# VerberBaby.net
KiCad netlist of a schematic drawn in EAGLE
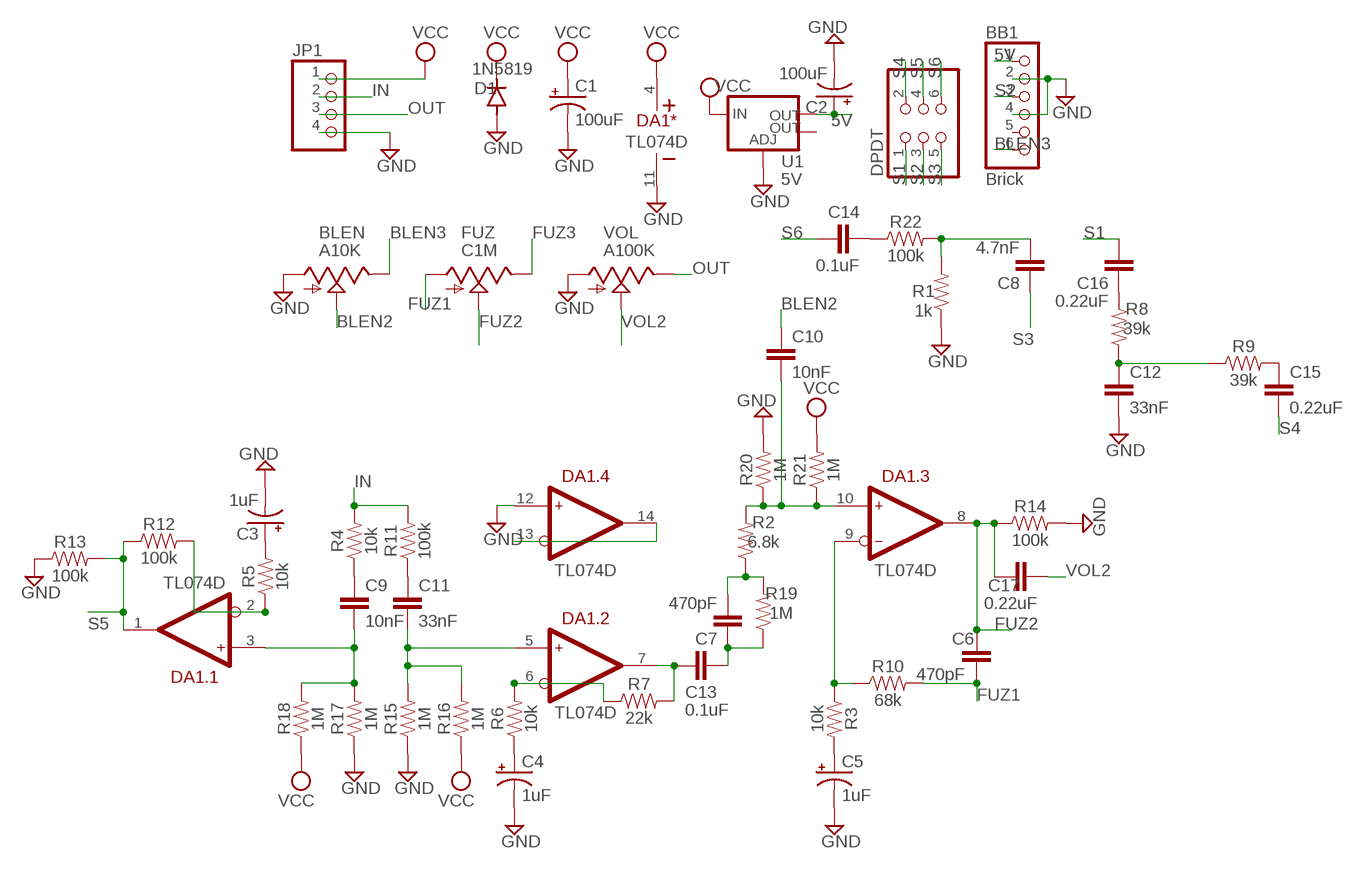
[diagram p0: schematic, sheet 1]

(export (version "E")
  (design (tool "Eeschema 10.0.6"))
  (components
    (comp (ref "BB1")
      (value "Brick")
      (footprint "eagle-import:1X06")
      (libsource (lib "eagle-import") (part "PINHD-1X6"))
    )
    (comp (ref "BLEN")
      (value "A10K")
      (footprint "eagle-import:9MM_SNAP-IN_POT")
      (libsource (lib "eagle-import") (part "9MM_SNAP-IN_POT_"))
    )
    (comp (ref "C1")
      (value "100uF")
      (footprint "eagle-import:PAN_B_SMD+THRU")
      (libsource (lib "eagle-import") (part "CAP_SMD+THRUPAN_B"))
    )
    (comp (ref "C2")
      (value "100uF")
      (footprint "eagle-import:PAN_B_SMD+THRU")
      (libsource (lib "eagle-import") (part "CAP_SMD+THRUPAN_B"))
    )
    (comp (ref "C3")
      (value "1uF")
      (footprint "eagle-import:PAN_B_SMD+THRU")
      (libsource (lib "eagle-import") (part "CAP_SMD+THRUPAN_B"))
    )
    (comp (ref "C4")
      (value "1uF")
      (footprint "eagle-import:PAN_B_SMD+THRU")
      (libsource (lib "eagle-import") (part "CAP_SMD+THRUPAN_B"))
    )
    (comp (ref "C5")
      (value "1uF")
      (footprint "eagle-import:PAN_B_SMD+THRU")
      (libsource (lib "eagle-import") (part "CAP_SMD+THRUPAN_B"))
    )
    (comp (ref "C6")
      (value "470pF")
      (footprint "eagle-import:0603")
      (libsource (lib "eagle-import") (part "470PF-0603-50V-5%"))
    )
    (comp (ref "C7")
      (value "470pF")
      (footprint "eagle-import:0603")
      (libsource (lib "eagle-import") (part "470PF-0603-50V-5%"))
    )
    (comp (ref "C8")
      (value "4.7nF")
      (footprint "eagle-import:0603")
      (libsource (lib "eagle-import") (part "4.7PF-0603-50V-5%"))
    )
    (comp (ref "C9")
      (value "10nF")
      (footprint "eagle-import:0603")
      (libsource (lib "eagle-import") (part "10NF-0603-50V-10%"))
    )
    (comp (ref "C10")
      (value "10nF")
      (footprint "eagle-import:0603")
      (libsource (lib "eagle-import") (part "10NF-0603-50V-10%"))
    )
    (comp (ref "C11")
      (value "33nF")
      (footprint "eagle-import:0603")
      (libsource (lib "eagle-import") (part "33NF-0603-50V-10%"))
    )
    (comp (ref "C12")
      (value "33nF")
      (footprint "eagle-import:0603")
      (libsource (lib "eagle-import") (part "33NF-0603-50V-10%"))
    )
    (comp (ref "C13")
      (value "0.1uF")
      (footprint "eagle-import:0603")
      (libsource (lib "eagle-import") (part "0.1UF-0603-25V-(+80/-20%)"))
    )
    (comp (ref "C14")
      (value "0.1uF")
      (footprint "eagle-import:0603")
      (libsource (lib "eagle-import") (part "0.1UF-0603-25V-(+80/-20%)"))
    )
    (comp (ref "C15")
      (value "0.22uF")
      (footprint "eagle-import:0603")
      (libsource (lib "eagle-import") (part "0.22UF-0603-25V-10%"))
    )
    (comp (ref "C16")
      (value "0.22uF")
      (footprint "eagle-import:0603")
      (libsource (lib "eagle-import") (part "0.22UF-0603-25V-10%"))
    )
    (comp (ref "C17")
      (value "0.22uF")
      (footprint "eagle-import:0603")
      (libsource (lib "eagle-import") (part "0.22UF-0603-25V-10%"))
    )
    (comp (ref "D1")
      (value "1N5819")
      (footprint "eagle-import:SOD123")
      (libsource (lib "eagle-import") (part "DIODE-SOD123"))
    )
    (comp (ref "DA1")
      (value "TL074D")
      (footprint "eagle-import:SO-14")
      (libsource (lib "eagle-import") (part "TL074D"))
    )
    (comp (ref "DPDT")
      (value "PINHD-2X3")
      (footprint "eagle-import:2X03")
      (libsource (lib "eagle-import") (part "PINHD-2X3"))
    )
    (comp (ref "FUZ")
      (value "C1M")
      (footprint "eagle-import:9MM_SNAP-IN_POT")
      (libsource (lib "eagle-import") (part "9MM_SNAP-IN_POT_"))
    )
    (comp (ref "JP1")
      (value "PINHD-1X4")
      (footprint "eagle-import:1X04")
      (libsource (lib "eagle-import") (part "PINHD-1X4"))
    )
    (comp (ref "R1")
      (value "1k")
      (footprint "eagle-import:0603")
      (libsource (lib "eagle-import") (part "1KOHM-0603-1/10W-1%"))
    )
    (comp (ref "R2")
      (value "6.8k")
      (footprint "eagle-import:0603")
      (libsource (lib "eagle-import") (part "6.8KOHM-0603-1/10W-1%"))
    )
    (comp (ref "R3")
      (value "10k")
      (footprint "eagle-import:0603")
      (libsource (lib "eagle-import") (part "10KOHM-0603-1/10W-1%"))
    )
    (comp (ref "R4")
      (value "10k")
      (footprint "eagle-import:0603")
      (libsource (lib "eagle-import") (part "10KOHM-0603-1/10W-1%"))
    )
    (comp (ref "R5")
      (value "10k")
      (footprint "eagle-import:0603")
      (libsource (lib "eagle-import") (part "10KOHM-0603-1/10W-1%"))
    )
    (comp (ref "R6")
      (value "10k")
      (footprint "eagle-import:0603")
      (libsource (lib "eagle-import") (part "10KOHM-0603-1/10W-1%"))
    )
    (comp (ref "R7")
      (value "22k")
      (footprint "eagle-import:0603")
      (libsource (lib "eagle-import") (part "22KOHM-0603-1/10W-1%"))
    )
    (comp (ref "R8")
      (value "39k")
      (footprint "eagle-import:0603")
      (libsource (lib "eagle-import") (part "39KOHM-0603-1/10W-1%"))
    )
    (comp (ref "R9")
      (value "39k")
      (footprint "eagle-import:0603")
      (libsource (lib "eagle-import") (part "39KOHM-0603-1/10W-1%"))
    )
    (comp (ref "R10")
      (value "68k")
      (footprint "eagle-import:0603")
      (libsource (lib "eagle-import") (part "68.1KOHM-0603-1/10W-1%"))
    )
    (comp (ref "R11")
      (value "100k")
      (footprint "eagle-import:0603")
      (libsource (lib "eagle-import") (part "100KOHM-0603-1/10W-1%"))
    )
    (comp (ref "R12")
      (value "100k")
      (footprint "eagle-import:0603")
      (libsource (lib "eagle-import") (part "100KOHM-0603-1/10W-1%"))
    )
    (comp (ref "R13")
      (value "100k")
      (footprint "eagle-import:0603")
      (libsource (lib "eagle-import") (part "100KOHM-0603-1/10W-1%"))
    )
    (comp (ref "R14")
      (value "100k")
      (footprint "eagle-import:0603")
      (libsource (lib "eagle-import") (part "100KOHM-0603-1/10W-1%"))
    )
    (comp (ref "R15")
      (value "1M")
      (footprint "eagle-import:0603")
      (libsource (lib "eagle-import") (part "1MOHM-0603-1/4W-5%"))
    )
    (comp (ref "R16")
      (value "1M")
      (footprint "eagle-import:0603")
      (libsource (lib "eagle-import") (part "1MOHM-0603-1/4W-5%"))
    )
    (comp (ref "R17")
      (value "1M")
      (footprint "eagle-import:0603")
      (libsource (lib "eagle-import") (part "1MOHM-0603-1/4W-5%"))
    )
    (comp (ref "R18")
      (value "1M")
      (footprint "eagle-import:0603")
      (libsource (lib "eagle-import") (part "1MOHM-0603-1/4W-5%"))
    )
    (comp (ref "R19")
      (value "1M")
      (footprint "eagle-import:0603")
      (libsource (lib "eagle-import") (part "1MOHM-0603-1/4W-5%"))
    )
    (comp (ref "R20")
      (value "1M")
      (footprint "eagle-import:0603")
      (libsource (lib "eagle-import") (part "1MOHM-0603-1/4W-5%"))
    )
    (comp (ref "R21")
      (value "1M")
      (footprint "eagle-import:0603")
      (libsource (lib "eagle-import") (part "1MOHM-0603-1/4W-5%"))
    )
    (comp (ref "R22")
      (value "100k")
      (footprint "eagle-import:0603")
      (libsource (lib "eagle-import") (part "100KOHM-0603-1/10W-1%"))
    )
    (comp (ref "U1")
      (value "5V")
      (footprint "eagle-import:SOT223")
      (libsource (lib "eagle-import") (part "V_REG_LM1117SOT223"))
    )
    (comp (ref "VOL")
      (value "A100K")
      (footprint "eagle-import:9MM_SNAP-IN_POT")
      (libsource (lib "eagle-import") (part "9MM_SNAP-IN_POT_"))
    )
  )
  (nets
    (net (code "1") (name "/5V") (class "Default")
      (node (ref "BB1") (pin "1") (pinfunction "1_1") (pintype "passive"))
      (node (ref "C2") (pin "+") (pinfunction "+_+") (pintype "passive"))
      (node (ref "C2") (pin "++") (pinfunction "+_++") (pintype "passive"))
      (node (ref "U1") (pin "2") (pinfunction "OUT_2") (pintype "output"))
    )
    (net (code "2") (name "/BLEN2") (class "Default")
      (node (ref "BLEN") (pin "2") (pinfunction "S_2") (pintype "passive"))
      (node (ref "C10") (pin "1") (pinfunction "1_1") (pintype "passive"))
    )
    (net (code "3") (name "/BLEN3") (class "Default")
      (node (ref "BB1") (pin "6") (pinfunction "6_6") (pintype "passive"))
      (node (ref "BLEN") (pin "3") (pinfunction "E_3") (pintype "passive"))
    )
    (net (code "4") (name "/FUZ1") (class "Default")
      (node (ref "C6") (pin "2") (pinfunction "2_2") (pintype "passive"))
      (node (ref "FUZ") (pin "1") (pinfunction "A_1") (pintype "passive"))
      (node (ref "R10") (pin "2") (pinfunction "2_2") (pintype "passive"))
    )
    (net (code "5") (name "/FUZ2") (class "Default")
      (node (ref "C17") (pin "1") (pinfunction "1_1") (pintype "passive"))
      (node (ref "C6") (pin "1") (pinfunction "1_1") (pintype "passive"))
      (node (ref "DA1") (pin "8") (pinfunction "OUT_8") (pintype "output"))
      (node (ref "FUZ") (pin "2") (pinfunction "S_2") (pintype "passive"))
      (node (ref "R14") (pin "1") (pinfunction "1_1") (pintype "passive"))
    )
    (net (code "6") (name "/FUZ3") (class "Default")
      (node (ref "FUZ") (pin "3") (pinfunction "E_3") (pintype "passive"))
    )
    (net (code "7") (name "/IN") (class "Default")
      (node (ref "JP1") (pin "2") (pinfunction "2_2") (pintype "passive"))
      (node (ref "R11") (pin "2") (pinfunction "2_2") (pintype "passive"))
      (node (ref "R4") (pin "2") (pinfunction "2_2") (pintype "passive"))
    )
    (net (code "8") (name "/OUT") (class "Default")
      (node (ref "JP1") (pin "3") (pinfunction "3_3") (pintype "passive"))
      (node (ref "VOL") (pin "3") (pinfunction "E_3") (pintype "passive"))
    )
    (net (code "9") (name "/S1") (class "Default")
      (node (ref "C16") (pin "2") (pinfunction "2_2") (pintype "passive"))
      (node (ref "DPDT") (pin "1") (pinfunction "1_1") (pintype "passive"))
    )
    (net (code "10") (name "/S2") (class "Default")
      (node (ref "BB1") (pin "3") (pinfunction "3_3") (pintype "passive"))
      (node (ref "DPDT") (pin "3") (pinfunction "3_3") (pintype "passive"))
    )
    (net (code "11") (name "/S3") (class "Default")
      (node (ref "C8") (pin "1") (pinfunction "1_1") (pintype "passive"))
      (node (ref "DPDT") (pin "5") (pinfunction "5_5") (pintype "passive"))
    )
    (net (code "12") (name "/S4") (class "Default")
      (node (ref "C15") (pin "2") (pinfunction "2_2") (pintype "passive"))
      (node (ref "DPDT") (pin "2") (pinfunction "2_2") (pintype "passive"))
    )
    (net (code "13") (name "/S5") (class "Default")
      (node (ref "DA1") (pin "1") (pinfunction "OUT_1") (pintype "output"))
      (node (ref "DPDT") (pin "4") (pinfunction "4_4") (pintype "passive"))
      (node (ref "R12") (pin "1") (pinfunction "1_1") (pintype "passive"))
      (node (ref "R13") (pin "2") (pinfunction "2_2") (pintype "passive"))
    )
    (net (code "14") (name "/S6") (class "Default")
      (node (ref "C14") (pin "1") (pinfunction "1_1") (pintype "passive"))
      (node (ref "DPDT") (pin "6") (pinfunction "6_6") (pintype "passive"))
    )
    (net (code "15") (name "/VOL2") (class "Default")
      (node (ref "C17") (pin "2") (pinfunction "2_2") (pintype "passive"))
      (node (ref "VOL") (pin "2") (pinfunction "S_2") (pintype "passive"))
    )
    (net (code "16") (name "GND") (class "Default")
      (node (ref "BB1") (pin "2") (pinfunction "2_2") (pintype "passive"))
      (node (ref "BB1") (pin "4") (pinfunction "4_4") (pintype "passive"))
      (node (ref "BLEN") (pin "1") (pinfunction "A_1") (pintype "passive"))
      (node (ref "C1") (pin "-") (pinfunction "-_-") (pintype "passive"))
      (node (ref "C1") (pin "--") (pinfunction "-_--") (pintype "passive"))
      (node (ref "C12") (pin "2") (pinfunction "2_2") (pintype "passive"))
      (node (ref "C2") (pin "-") (pinfunction "-_-") (pintype "passive"))
      (node (ref "C2") (pin "--") (pinfunction "-_--") (pintype "passive"))
      (node (ref "C3") (pin "-") (pinfunction "-_-") (pintype "passive"))
      (node (ref "C3") (pin "--") (pinfunction "-_--") (pintype "passive"))
      (node (ref "C4") (pin "-") (pinfunction "-_-") (pintype "passive"))
      (node (ref "C4") (pin "--") (pinfunction "-_--") (pintype "passive"))
      (node (ref "C5") (pin "-") (pinfunction "-_-") (pintype "passive"))
      (node (ref "C5") (pin "--") (pinfunction "-_--") (pintype "passive"))
      (node (ref "D1") (pin "A") (pinfunction "A_A") (pintype "passive"))
      (node (ref "DA1") (pin "11") (pinfunction "V-_11") (pintype "power_in"))
      (node (ref "DA1") (pin "12") (pinfunction "IN+_12") (pintype "input"))
      (node (ref "JP1") (pin "4") (pinfunction "4_4") (pintype "passive"))
      (node (ref "R1") (pin "1") (pinfunction "1_1") (pintype "passive"))
      (node (ref "R13") (pin "1") (pinfunction "1_1") (pintype "passive"))
      (node (ref "R14") (pin "2") (pinfunction "2_2") (pintype "passive"))
      (node (ref "R15") (pin "1") (pinfunction "1_1") (pintype "passive"))
      (node (ref "R17") (pin "1") (pinfunction "1_1") (pintype "passive"))
      (node (ref "R20") (pin "2") (pinfunction "2_2") (pintype "passive"))
      (node (ref "U1") (pin "1") (pinfunction "ADJ_1") (pintype "input"))
      (node (ref "VOL") (pin "1") (pinfunction "A_1") (pintype "passive"))
    )
    (net (code "17") (name "Net-(C3-+-Pad++)") (class "Default")
      (node (ref "C3") (pin "+") (pinfunction "+_+") (pintype "passive"))
      (node (ref "C3") (pin "++") (pinfunction "+_++") (pintype "passive"))
      (node (ref "R5") (pin "2") (pinfunction "2_2") (pintype "passive"))
    )
    (net (code "18") (name "Net-(C4-+-Pad++)") (class "Default")
      (node (ref "C4") (pin "+") (pinfunction "+_+") (pintype "passive"))
      (node (ref "C4") (pin "++") (pinfunction "+_++") (pintype "passive"))
      (node (ref "R6") (pin "1") (pinfunction "1_1") (pintype "passive"))
    )
    (net (code "19") (name "Net-(C5-+-Pad++)") (class "Default")
      (node (ref "C5") (pin "+") (pinfunction "+_+") (pintype "passive"))
      (node (ref "C5") (pin "++") (pinfunction "+_++") (pintype "passive"))
      (node (ref "R3") (pin "2") (pinfunction "2_2") (pintype "passive"))
    )
    (net (code "20") (name "Net-(C7-Pad2)") (class "Default")
      (node (ref "C7") (pin "2") (pinfunction "2_2") (pintype "passive"))
      (node (ref "R19") (pin "2") (pinfunction "2_2") (pintype "passive"))
      (node (ref "R2") (pin "1") (pinfunction "1_1") (pintype "passive"))
    )
    (net (code "21") (name "Net-(C8-Pad2)") (class "Default")
      (node (ref "C8") (pin "2") (pinfunction "2_2") (pintype "passive"))
      (node (ref "R1") (pin "2") (pinfunction "2_2") (pintype "passive"))
      (node (ref "R22") (pin "2") (pinfunction "2_2") (pintype "passive"))
    )
    (net (code "22") (name "Net-(C9-Pad1)") (class "Default")
      (node (ref "C9") (pin "1") (pinfunction "1_1") (pintype "passive"))
      (node (ref "R4") (pin "1") (pinfunction "1_1") (pintype "passive"))
    )
    (net (code "23") (name "Net-(C11-Pad1)") (class "Default")
      (node (ref "C11") (pin "1") (pinfunction "1_1") (pintype "passive"))
      (node (ref "R11") (pin "1") (pinfunction "1_1") (pintype "passive"))
    )
    (net (code "24") (name "Net-(C12-Pad1)") (class "Default")
      (node (ref "C12") (pin "1") (pinfunction "1_1") (pintype "passive"))
      (node (ref "R8") (pin "1") (pinfunction "1_1") (pintype "passive"))
      (node (ref "R9") (pin "1") (pinfunction "1_1") (pintype "passive"))
    )
    (net (code "25") (name "Net-(C13-Pad1)") (class "Default")
      (node (ref "C13") (pin "1") (pinfunction "1_1") (pintype "passive"))
      (node (ref "C7") (pin "1") (pinfunction "1_1") (pintype "passive"))
      (node (ref "R19") (pin "1") (pinfunction "1_1") (pintype "passive"))
    )
    (net (code "26") (name "Net-(C14-Pad2)") (class "Default")
      (node (ref "C14") (pin "2") (pinfunction "2_2") (pintype "passive"))
      (node (ref "R22") (pin "1") (pinfunction "1_1") (pintype "passive"))
    )
    (net (code "27") (name "Net-(C15-Pad1)") (class "Default")
      (node (ref "C15") (pin "1") (pinfunction "1_1") (pintype "passive"))
      (node (ref "R9") (pin "2") (pinfunction "2_2") (pintype "passive"))
    )
    (net (code "28") (name "Net-(C16-Pad1)") (class "Default")
      (node (ref "C16") (pin "1") (pinfunction "1_1") (pintype "passive"))
      (node (ref "R8") (pin "2") (pinfunction "2_2") (pintype "passive"))
    )
    (net (code "29") (name "Net-(DA1B-IN+)") (class "Default")
      (node (ref "C9") (pin "2") (pinfunction "2_2") (pintype "passive"))
      (node (ref "DA1") (pin "3") (pinfunction "IN+_3") (pintype "input"))
      (node (ref "R17") (pin "2") (pinfunction "2_2") (pintype "passive"))
      (node (ref "R18") (pin "2") (pinfunction "2_2") (pintype "passive"))
    )
    (net (code "30") (name "Net-(DA1B-IN-)") (class "Default")
      (node (ref "DA1") (pin "2") (pinfunction "IN-_2") (pintype "input"))
      (node (ref "R12") (pin "2") (pinfunction "2_2") (pintype "passive"))
      (node (ref "R5") (pin "1") (pinfunction "1_1") (pintype "passive"))
    )
    (net (code "31") (name "Net-(DA1C-IN+)") (class "Default")
      (node (ref "C11") (pin "2") (pinfunction "2_2") (pintype "passive"))
      (node (ref "DA1") (pin "5") (pinfunction "IN+_5") (pintype "input"))
      (node (ref "R15") (pin "2") (pinfunction "2_2") (pintype "passive"))
      (node (ref "R16") (pin "2") (pinfunction "2_2") (pintype "passive"))
    )
    (net (code "32") (name "Net-(DA1C-IN-)") (class "Default")
      (node (ref "DA1") (pin "6") (pinfunction "IN-_6") (pintype "input"))
      (node (ref "R6") (pin "2") (pinfunction "2_2") (pintype "passive"))
      (node (ref "R7") (pin "1") (pinfunction "1_1") (pintype "passive"))
    )
    (net (code "33") (name "Net-(DA1C-OUT)") (class "Default")
      (node (ref "C13") (pin "2") (pinfunction "2_2") (pintype "passive"))
      (node (ref "DA1") (pin "7") (pinfunction "OUT_7") (pintype "output"))
      (node (ref "R7") (pin "2") (pinfunction "2_2") (pintype "passive"))
    )
    (net (code "34") (name "Net-(DA1D-IN+)") (class "Default")
      (node (ref "C10") (pin "2") (pinfunction "2_2") (pintype "passive"))
      (node (ref "DA1") (pin "10") (pinfunction "IN+_10") (pintype "input"))
      (node (ref "R2") (pin "2") (pinfunction "2_2") (pintype "passive"))
      (node (ref "R20") (pin "1") (pinfunction "1_1") (pintype "passive"))
      (node (ref "R21") (pin "1") (pinfunction "1_1") (pintype "passive"))
    )
    (net (code "35") (name "Net-(DA1D-IN-)") (class "Default")
      (node (ref "DA1") (pin "9") (pinfunction "IN-_9") (pintype "input"))
      (node (ref "R10") (pin "1") (pinfunction "1_1") (pintype "passive"))
      (node (ref "R3") (pin "1") (pinfunction "1_1") (pintype "passive"))
    )
    (net (code "36") (name "Net-(DA1E-IN-)") (class "Default")
      (node (ref "DA1") (pin "13") (pinfunction "IN-_13") (pintype "input"))
      (node (ref "DA1") (pin "14") (pinfunction "OUT_14") (pintype "output"))
    )
    (net (code "37") (name "VCC") (class "Default")
      (node (ref "C1") (pin "+") (pinfunction "+_+") (pintype "passive"))
      (node (ref "C1") (pin "++") (pinfunction "+_++") (pintype "passive"))
      (node (ref "D1") (pin "C") (pinfunction "C_C") (pintype "passive"))
      (node (ref "DA1") (pin "4") (pinfunction "V+_4") (pintype "power_in"))
      (node (ref "JP1") (pin "1") (pinfunction "1_1") (pintype "passive"))
      (node (ref "R16") (pin "1") (pinfunction "1_1") (pintype "passive"))
      (node (ref "R18") (pin "1") (pinfunction "1_1") (pintype "passive"))
      (node (ref "R21") (pin "2") (pinfunction "2_2") (pintype "passive"))
      (node (ref "U1") (pin "3") (pinfunction "IN_3") (pintype "input"))
    )
    (net (code "38") (name "unconnected-(BB1-Pad5)") (class "Default")
      (node (ref "BB1") (pin "5") (pinfunction "5_5") (pintype "passive"))
    )
    (net (code "39") (name "unconnected-(U1-OUT-Pad4)") (class "Default")
      (node (ref "U1") (pin "4") (pinfunction "OUT_4") (pintype "output"))
    )
  )
)
